# schemat.net
KiCad netlist of a schematic drawn in EAGLE
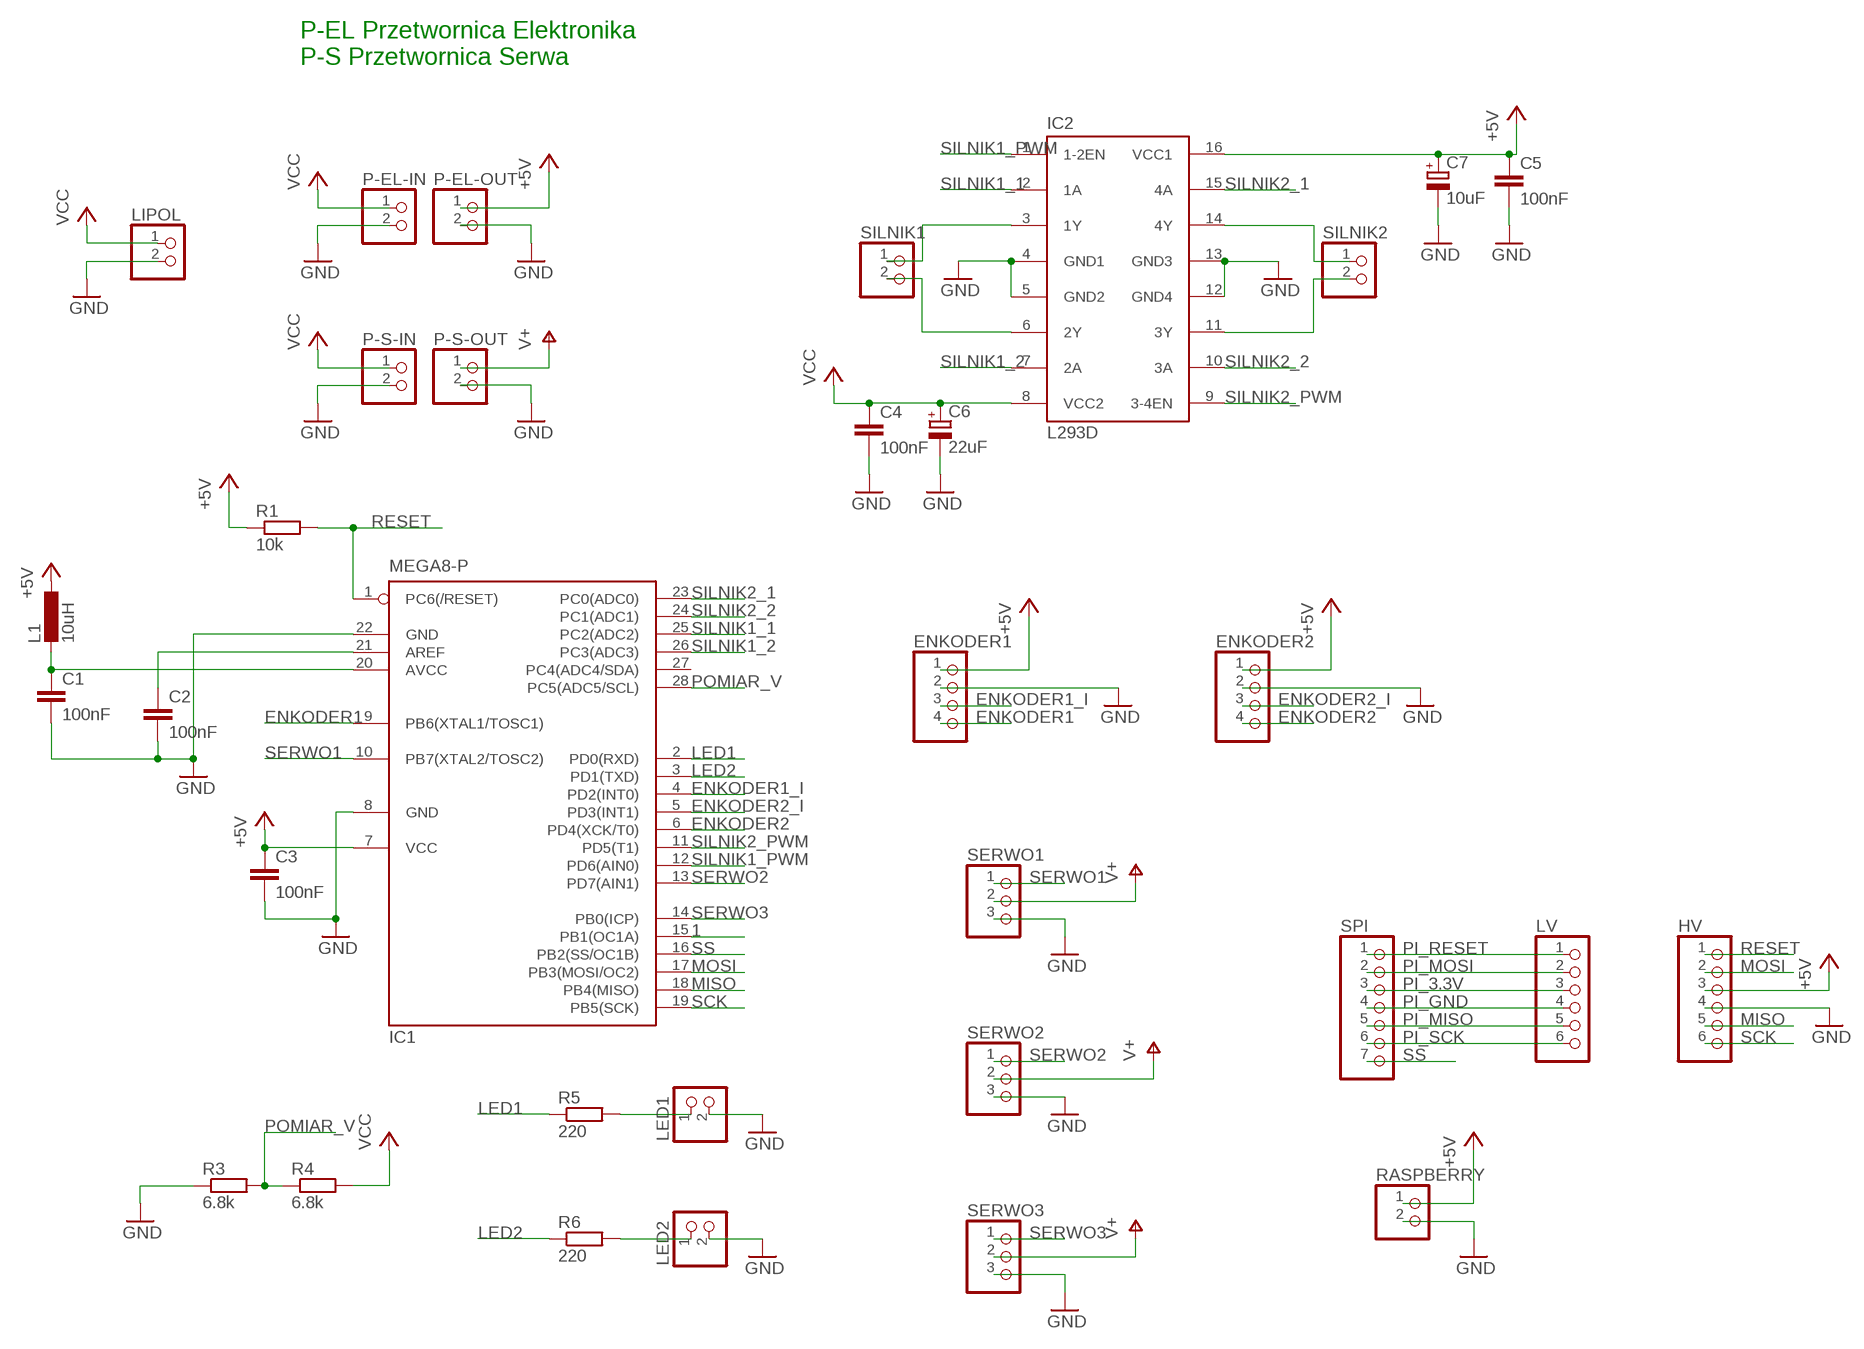
[diagram p0: schematic, sheet 1]

(export (version "E")
  (design (tool "Eeschema 10.0.6"))
  (components
    (comp (ref "C1")
      (value "100nF")
      (footprint "eagle-import:C050-030X075")
      (libsource (lib "eagle-import") (part "C-EU050-030X075"))
    )
    (comp (ref "C2")
      (value "100nF")
      (footprint "eagle-import:C025-030X050")
      (libsource (lib "eagle-import") (part "C-EU025-030X050"))
    )
    (comp (ref "C3")
      (value "100nF")
      (footprint "eagle-import:C025-030X050")
      (libsource (lib "eagle-import") (part "C-EU025-030X050"))
    )
    (comp (ref "C4")
      (value "100nF")
      (footprint "eagle-import:C025-030X050")
      (libsource (lib "eagle-import") (part "C-EU025-030X050"))
    )
    (comp (ref "C5")
      (value "100nF")
      (footprint "eagle-import:C025-030X050")
      (libsource (lib "eagle-import") (part "C-EU025-030X050"))
    )
    (comp (ref "C6")
      (value "22uF")
      (footprint "eagle-import:E2,5-5")
      (libsource (lib "eagle-import") (part "CPOL-EUE2.5-5"))
    )
    (comp (ref "C7")
      (value "10uF")
      (footprint "eagle-import:E2,5-5")
      (libsource (lib "eagle-import") (part "CPOL-EUE2.5-5"))
    )
    (comp (ref "ENKODER1")
      (value "PINHD-1X4")
      (footprint "eagle-import:1X04")
      (libsource (lib "eagle-import") (part "PINHD-1X4"))
    )
    (comp (ref "ENKODER2")
      (value "PINHD-1X4")
      (footprint "eagle-import:1X04")
      (libsource (lib "eagle-import") (part "PINHD-1X4"))
    )
    (comp (ref "HV")
      (value "PINHD-1X6")
      (footprint "eagle-import:1X06")
      (libsource (lib "eagle-import") (part "PINHD-1X6"))
    )
    (comp (ref "IC1")
      (value "MEGA8-P")
      (footprint "eagle-import:DIL28-3")
      (libsource (lib "eagle-import") (part "MEGA8-P"))
    )
    (comp (ref "IC2")
      (value "L293D")
      (footprint "eagle-import:DIL16")
      (libsource (lib "eagle-import") (part "L293D"))
    )
    (comp (ref "L1")
      (value "10uH")
      (footprint "eagle-import:0204_7")
      (libsource (lib "eagle-import") (part "L-EU0204/7"))
    )
    (comp (ref "LED1")
      (value "PINHD-1X2")
      (footprint "eagle-import:1X02")
      (libsource (lib "eagle-import") (part "PINHD-1X2"))
    )
    (comp (ref "LED2")
      (value "PINHD-1X2")
      (footprint "eagle-import:1X02")
      (libsource (lib "eagle-import") (part "PINHD-1X2"))
    )
    (comp (ref "LIPOL")
      (value "PINHD-1X2")
      (footprint "eagle-import:1X02")
      (libsource (lib "eagle-import") (part "PINHD-1X2"))
    )
    (comp (ref "LV")
      (value "PINHD-1X6")
      (footprint "eagle-import:1X06")
      (libsource (lib "eagle-import") (part "PINHD-1X6"))
    )
    (comp (ref "P-EL-IN")
      (value "PINHD-1X2")
      (footprint "eagle-import:1X02")
      (libsource (lib "eagle-import") (part "PINHD-1X2"))
    )
    (comp (ref "P-EL-OUT")
      (value "PINHD-1X2")
      (footprint "eagle-import:1X02")
      (libsource (lib "eagle-import") (part "PINHD-1X2"))
    )
    (comp (ref "P-S-IN")
      (value "PINHD-1X2")
      (footprint "eagle-import:1X02")
      (libsource (lib "eagle-import") (part "PINHD-1X2"))
    )
    (comp (ref "P-S-OUT")
      (value "PINHD-1X2")
      (footprint "eagle-import:1X02")
      (libsource (lib "eagle-import") (part "PINHD-1X2"))
    )
    (comp (ref "R1")
      (value "10k")
      (footprint "eagle-import:0204_7")
      (libsource (lib "eagle-import") (part "R-EU_0204/7"))
    )
    (comp (ref "R3")
      (value "6.8k")
      (footprint "eagle-import:0204_7")
      (libsource (lib "eagle-import") (part "R-EU_0204/7"))
    )
    (comp (ref "R4")
      (value "6.8k")
      (footprint "eagle-import:0204_7")
      (libsource (lib "eagle-import") (part "R-EU_0204/7"))
    )
    (comp (ref "R5")
      (value "220")
      (footprint "eagle-import:0204_7")
      (libsource (lib "eagle-import") (part "R-EU_0204/7"))
    )
    (comp (ref "R6")
      (value "220")
      (footprint "eagle-import:0204_7")
      (libsource (lib "eagle-import") (part "R-EU_0204/7"))
    )
    (comp (ref "RASPBERRY")
      (value "PINHD-1X2")
      (footprint "eagle-import:1X02")
      (libsource (lib "eagle-import") (part "PINHD-1X2"))
    )
    (comp (ref "SERWO1")
      (value "PINHD-1X3")
      (footprint "eagle-import:1X03")
      (libsource (lib "eagle-import") (part "PINHD-1X3"))
    )
    (comp (ref "SERWO2")
      (value "PINHD-1X3")
      (footprint "eagle-import:1X03")
      (libsource (lib "eagle-import") (part "PINHD-1X3"))
    )
    (comp (ref "SERWO3")
      (value "PINHD-1X3")
      (footprint "eagle-import:1X03")
      (libsource (lib "eagle-import") (part "PINHD-1X3"))
    )
    (comp (ref "SILNIK1")
      (value "PINHD-1X2")
      (footprint "eagle-import:1X02")
      (libsource (lib "eagle-import") (part "PINHD-1X2"))
    )
    (comp (ref "SILNIK2")
      (value "PINHD-1X2")
      (footprint "eagle-import:1X02")
      (libsource (lib "eagle-import") (part "PINHD-1X2"))
    )
    (comp (ref "SPI")
      (value "PINHD-1X7")
      (footprint "eagle-import:1X07")
      (libsource (lib "eagle-import") (part "PINHD-1X7"))
    )
  )
  (nets
    (net (code "1") (name "+5V") (class "Default")
      (node (ref "C3") (pin "1") (pinfunction "1_1") (pintype "passive"))
      (node (ref "C5") (pin "1") (pinfunction "1_1") (pintype "passive"))
      (node (ref "C7") (pin "+") (pinfunction "+_+") (pintype "passive"))
      (node (ref "ENKODER1") (pin "1") (pinfunction "1_1") (pintype "passive"))
      (node (ref "ENKODER2") (pin "1") (pinfunction "1_1") (pintype "passive"))
      (node (ref "HV") (pin "3") (pinfunction "3_3") (pintype "passive"))
      (node (ref "IC1") (pin "7") (pinfunction "VCC_7") (pintype "power_in"))
      (node (ref "IC2") (pin "16") (pinfunction "VCC1_16") (pintype "power_in"))
      (node (ref "L1") (pin "1") (pinfunction "1_1") (pintype "passive"))
      (node (ref "P-EL-OUT") (pin "1") (pinfunction "1_1") (pintype "passive"))
      (node (ref "R1") (pin "1") (pinfunction "1_1") (pintype "passive"))
      (node (ref "RASPBERRY") (pin "1") (pinfunction "1_1") (pintype "passive"))
    )
    (net (code "2") (name "/1") (class "Default")
      (node (ref "IC1") (pin "15") (pinfunction "PB1(OC1A)_15") (pintype "bidirectional"))
    )
    (net (code "3") (name "/ENKODER1") (class "Default")
      (node (ref "ENKODER1") (pin "4") (pinfunction "4_4") (pintype "passive"))
      (node (ref "IC1") (pin "9") (pinfunction "PB6(XTAL1/TOSC1)_9") (pintype "bidirectional"))
    )
    (net (code "4") (name "/ENKODER1_I") (class "Default")
      (node (ref "ENKODER1") (pin "3") (pinfunction "3_3") (pintype "passive"))
      (node (ref "IC1") (pin "4") (pinfunction "PD2(INT0)_4") (pintype "bidirectional"))
    )
    (net (code "5") (name "/ENKODER2") (class "Default")
      (node (ref "ENKODER2") (pin "4") (pinfunction "4_4") (pintype "passive"))
      (node (ref "IC1") (pin "6") (pinfunction "PD4(XCK/T0)_6") (pintype "bidirectional"))
    )
    (net (code "6") (name "/ENKODER2_I") (class "Default")
      (node (ref "ENKODER2") (pin "3") (pinfunction "3_3") (pintype "passive"))
      (node (ref "IC1") (pin "5") (pinfunction "PD3(INT1)_5") (pintype "bidirectional"))
    )
    (net (code "7") (name "/LED1") (class "Default")
      (node (ref "IC1") (pin "2") (pinfunction "PD0(RXD)_2") (pintype "bidirectional"))
      (node (ref "R5") (pin "1") (pinfunction "1_1") (pintype "passive"))
    )
    (net (code "8") (name "/LED2") (class "Default")
      (node (ref "IC1") (pin "3") (pinfunction "PD1(TXD)_3") (pintype "bidirectional"))
      (node (ref "R6") (pin "1") (pinfunction "1_1") (pintype "passive"))
    )
    (net (code "9") (name "/MISO") (class "Default")
      (node (ref "HV") (pin "5") (pinfunction "5_5") (pintype "passive"))
      (node (ref "IC1") (pin "18") (pinfunction "PB4(MISO)_18") (pintype "bidirectional"))
    )
    (net (code "10") (name "/MOSI") (class "Default")
      (node (ref "HV") (pin "2") (pinfunction "2_2") (pintype "passive"))
      (node (ref "IC1") (pin "17") (pinfunction "PB3(MOSI/OC2)_17") (pintype "bidirectional"))
    )
    (net (code "11") (name "/PI_3.3V") (class "Default")
      (node (ref "LV") (pin "3") (pinfunction "3_3") (pintype "passive"))
      (node (ref "SPI") (pin "3") (pinfunction "3_3") (pintype "passive"))
    )
    (net (code "12") (name "/PI_GND") (class "Default")
      (node (ref "LV") (pin "4") (pinfunction "4_4") (pintype "passive"))
      (node (ref "SPI") (pin "4") (pinfunction "4_4") (pintype "passive"))
    )
    (net (code "13") (name "/PI_MISO") (class "Default")
      (node (ref "LV") (pin "5") (pinfunction "5_5") (pintype "passive"))
      (node (ref "SPI") (pin "5") (pinfunction "5_5") (pintype "passive"))
    )
    (net (code "14") (name "/PI_MOSI") (class "Default")
      (node (ref "LV") (pin "2") (pinfunction "2_2") (pintype "passive"))
      (node (ref "SPI") (pin "2") (pinfunction "2_2") (pintype "passive"))
    )
    (net (code "15") (name "/PI_RESET") (class "Default")
      (node (ref "LV") (pin "1") (pinfunction "1_1") (pintype "passive"))
      (node (ref "SPI") (pin "1") (pinfunction "1_1") (pintype "passive"))
    )
    (net (code "16") (name "/PI_SCK") (class "Default")
      (node (ref "LV") (pin "6") (pinfunction "6_6") (pintype "passive"))
      (node (ref "SPI") (pin "6") (pinfunction "6_6") (pintype "passive"))
    )
    (net (code "17") (name "/POMIAR_V") (class "Default")
      (node (ref "IC1") (pin "28") (pinfunction "PC5(ADC5/SCL)_28") (pintype "bidirectional"))
      (node (ref "R3") (pin "2") (pinfunction "2_2") (pintype "passive"))
      (node (ref "R4") (pin "1") (pinfunction "1_1") (pintype "passive"))
    )
    (net (code "18") (name "/RESET") (class "Default")
      (node (ref "HV") (pin "1") (pinfunction "1_1") (pintype "passive"))
      (node (ref "IC1") (pin "1") (pinfunction "PC6(/RESET)_1") (pintype "bidirectional"))
      (node (ref "R1") (pin "2") (pinfunction "2_2") (pintype "passive"))
    )
    (net (code "19") (name "/SCK") (class "Default")
      (node (ref "HV") (pin "6") (pinfunction "6_6") (pintype "passive"))
      (node (ref "IC1") (pin "19") (pinfunction "PB5(SCK)_19") (pintype "bidirectional"))
    )
    (net (code "20") (name "/SERWO1") (class "Default")
      (node (ref "IC1") (pin "10") (pinfunction "PB7(XTAL2/TOSC2)_10") (pintype "bidirectional"))
      (node (ref "SERWO1") (pin "1") (pinfunction "1_1") (pintype "passive"))
    )
    (net (code "21") (name "/SERWO2") (class "Default")
      (node (ref "IC1") (pin "13") (pinfunction "PD7(AIN1)_13") (pintype "bidirectional"))
      (node (ref "SERWO2") (pin "1") (pinfunction "1_1") (pintype "passive"))
    )
    (net (code "22") (name "/SERWO3") (class "Default")
      (node (ref "IC1") (pin "14") (pinfunction "PB0(ICP)_14") (pintype "bidirectional"))
      (node (ref "SERWO3") (pin "1") (pinfunction "1_1") (pintype "passive"))
    )
    (net (code "23") (name "/SILNIK1_1") (class "Default")
      (node (ref "IC1") (pin "25") (pinfunction "PC2(ADC2)_25") (pintype "bidirectional"))
      (node (ref "IC2") (pin "2") (pinfunction "1A_2") (pintype "input"))
    )
    (net (code "24") (name "/SILNIK1_2") (class "Default")
      (node (ref "IC1") (pin "26") (pinfunction "PC3(ADC3)_26") (pintype "bidirectional"))
      (node (ref "IC2") (pin "7") (pinfunction "2A_7") (pintype "input"))
    )
    (net (code "25") (name "/SILNIK1_PWM") (class "Default")
      (node (ref "IC1") (pin "12") (pinfunction "PD6(AIN0)_12") (pintype "bidirectional"))
      (node (ref "IC2") (pin "1") (pinfunction "1-2EN_1") (pintype "input"))
    )
    (net (code "26") (name "/SILNIK2_1") (class "Default")
      (node (ref "IC1") (pin "23") (pinfunction "PC0(ADC0)_23") (pintype "bidirectional"))
      (node (ref "IC2") (pin "15") (pinfunction "4A_15") (pintype "input"))
    )
    (net (code "27") (name "/SILNIK2_2") (class "Default")
      (node (ref "IC1") (pin "24") (pinfunction "PC1(ADC1)_24") (pintype "bidirectional"))
      (node (ref "IC2") (pin "10") (pinfunction "3A_10") (pintype "input"))
    )
    (net (code "28") (name "/SILNIK2_PWM") (class "Default")
      (node (ref "IC1") (pin "11") (pinfunction "PD5(T1)_11") (pintype "bidirectional"))
      (node (ref "IC2") (pin "9") (pinfunction "3-4EN_9") (pintype "input"))
    )
    (net (code "29") (name "/SS") (class "Default")
      (node (ref "IC1") (pin "16") (pinfunction "PB2(SS/OC1B)_16") (pintype "bidirectional"))
      (node (ref "SPI") (pin "7") (pinfunction "7_7") (pintype "passive"))
    )
    (net (code "30") (name "GND") (class "Default")
      (node (ref "C1") (pin "2") (pinfunction "2_2") (pintype "passive"))
      (node (ref "C2") (pin "2") (pinfunction "2_2") (pintype "passive"))
      (node (ref "C3") (pin "2") (pinfunction "2_2") (pintype "passive"))
      (node (ref "C4") (pin "2") (pinfunction "2_2") (pintype "passive"))
      (node (ref "C5") (pin "2") (pinfunction "2_2") (pintype "passive"))
      (node (ref "C6") (pin "-") (pinfunction "-_-") (pintype "passive"))
      (node (ref "C7") (pin "-") (pinfunction "-_-") (pintype "passive"))
      (node (ref "ENKODER1") (pin "2") (pinfunction "2_2") (pintype "passive"))
      (node (ref "ENKODER2") (pin "2") (pinfunction "2_2") (pintype "passive"))
      (node (ref "HV") (pin "4") (pinfunction "4_4") (pintype "passive"))
      (node (ref "IC1") (pin "22") (pinfunction "GND_22") (pintype "power_in"))
      (node (ref "IC1") (pin "8") (pinfunction "GND_8") (pintype "power_in"))
      (node (ref "IC2") (pin "12") (pinfunction "GND4_12") (pintype "power_in"))
      (node (ref "IC2") (pin "13") (pinfunction "GND3_13") (pintype "power_in"))
      (node (ref "IC2") (pin "4") (pinfunction "GND1_4") (pintype "power_in"))
      (node (ref "IC2") (pin "5") (pinfunction "GND2_5") (pintype "power_in"))
      (node (ref "LED1") (pin "2") (pinfunction "2_2") (pintype "passive"))
      (node (ref "LED2") (pin "2") (pinfunction "2_2") (pintype "passive"))
      (node (ref "LIPOL") (pin "2") (pinfunction "2_2") (pintype "passive"))
      (node (ref "P-EL-IN") (pin "2") (pinfunction "2_2") (pintype "passive"))
      (node (ref "P-EL-OUT") (pin "2") (pinfunction "2_2") (pintype "passive"))
      (node (ref "P-S-IN") (pin "2") (pinfunction "2_2") (pintype "passive"))
      (node (ref "P-S-OUT") (pin "2") (pinfunction "2_2") (pintype "passive"))
      (node (ref "R3") (pin "1") (pinfunction "1_1") (pintype "passive"))
      (node (ref "RASPBERRY") (pin "2") (pinfunction "2_2") (pintype "passive"))
      (node (ref "SERWO1") (pin "3") (pinfunction "3_3") (pintype "passive"))
      (node (ref "SERWO2") (pin "3") (pinfunction "3_3") (pintype "passive"))
      (node (ref "SERWO3") (pin "3") (pinfunction "3_3") (pintype "passive"))
    )
    (net (code "31") (name "Net-(IC1-AREF)") (class "Default")
      (node (ref "C2") (pin "1") (pinfunction "1_1") (pintype "passive"))
      (node (ref "IC1") (pin "21") (pinfunction "AREF_21") (pintype "passive"))
    )
    (net (code "32") (name "Net-(IC1-AVCC)") (class "Default")
      (node (ref "C1") (pin "1") (pinfunction "1_1") (pintype "passive"))
      (node (ref "IC1") (pin "20") (pinfunction "AVCC_20") (pintype "power_in"))
      (node (ref "L1") (pin "2") (pinfunction "2_2") (pintype "passive"))
    )
    (net (code "33") (name "Net-(IC2-1Y)") (class "Default")
      (node (ref "IC2") (pin "3") (pinfunction "1Y_3") (pintype "output"))
      (node (ref "SILNIK1") (pin "1") (pinfunction "1_1") (pintype "passive"))
    )
    (net (code "34") (name "Net-(IC2-2Y)") (class "Default")
      (node (ref "IC2") (pin "6") (pinfunction "2Y_6") (pintype "output"))
      (node (ref "SILNIK1") (pin "2") (pinfunction "2_2") (pintype "passive"))
    )
    (net (code "35") (name "Net-(IC2-3Y)") (class "Default")
      (node (ref "IC2") (pin "11") (pinfunction "3Y_11") (pintype "output"))
      (node (ref "SILNIK2") (pin "2") (pinfunction "2_2") (pintype "passive"))
    )
    (net (code "36") (name "Net-(IC2-4Y)") (class "Default")
      (node (ref "IC2") (pin "14") (pinfunction "4Y_14") (pintype "output"))
      (node (ref "SILNIK2") (pin "1") (pinfunction "1_1") (pintype "passive"))
    )
    (net (code "37") (name "Net-(LED1-Pad1)") (class "Default")
      (node (ref "LED1") (pin "1") (pinfunction "1_1") (pintype "passive"))
      (node (ref "R5") (pin "2") (pinfunction "2_2") (pintype "passive"))
    )
    (net (code "38") (name "Net-(LED2-Pad1)") (class "Default")
      (node (ref "LED2") (pin "1") (pinfunction "1_1") (pintype "passive"))
      (node (ref "R6") (pin "2") (pinfunction "2_2") (pintype "passive"))
    )
    (net (code "39") (name "V+") (class "Default")
      (node (ref "P-S-OUT") (pin "1") (pinfunction "1_1") (pintype "passive"))
      (node (ref "SERWO1") (pin "2") (pinfunction "2_2") (pintype "passive"))
      (node (ref "SERWO2") (pin "2") (pinfunction "2_2") (pintype "passive"))
      (node (ref "SERWO3") (pin "2") (pinfunction "2_2") (pintype "passive"))
    )
    (net (code "40") (name "VCC") (class "Default")
      (node (ref "C4") (pin "1") (pinfunction "1_1") (pintype "passive"))
      (node (ref "C6") (pin "+") (pinfunction "+_+") (pintype "passive"))
      (node (ref "IC2") (pin "8") (pinfunction "VCC2_8") (pintype "power_in"))
      (node (ref "LIPOL") (pin "1") (pinfunction "1_1") (pintype "passive"))
      (node (ref "P-EL-IN") (pin "1") (pinfunction "1_1") (pintype "passive"))
      (node (ref "P-S-IN") (pin "1") (pinfunction "1_1") (pintype "passive"))
      (node (ref "R4") (pin "2") (pinfunction "2_2") (pintype "passive"))
    )
    (net (code "41") (name "unconnected-(IC1-PC4(ADC4{slash}SDA)-Pad27)") (class "Default")
      (node (ref "IC1") (pin "27") (pinfunction "PC4(ADC4/SDA)_27") (pintype "bidirectional"))
    )
  )
)
